# Auto_Temp_Sensor_Second_Way.net
KiCad netlist of a schematic drawn in EAGLE
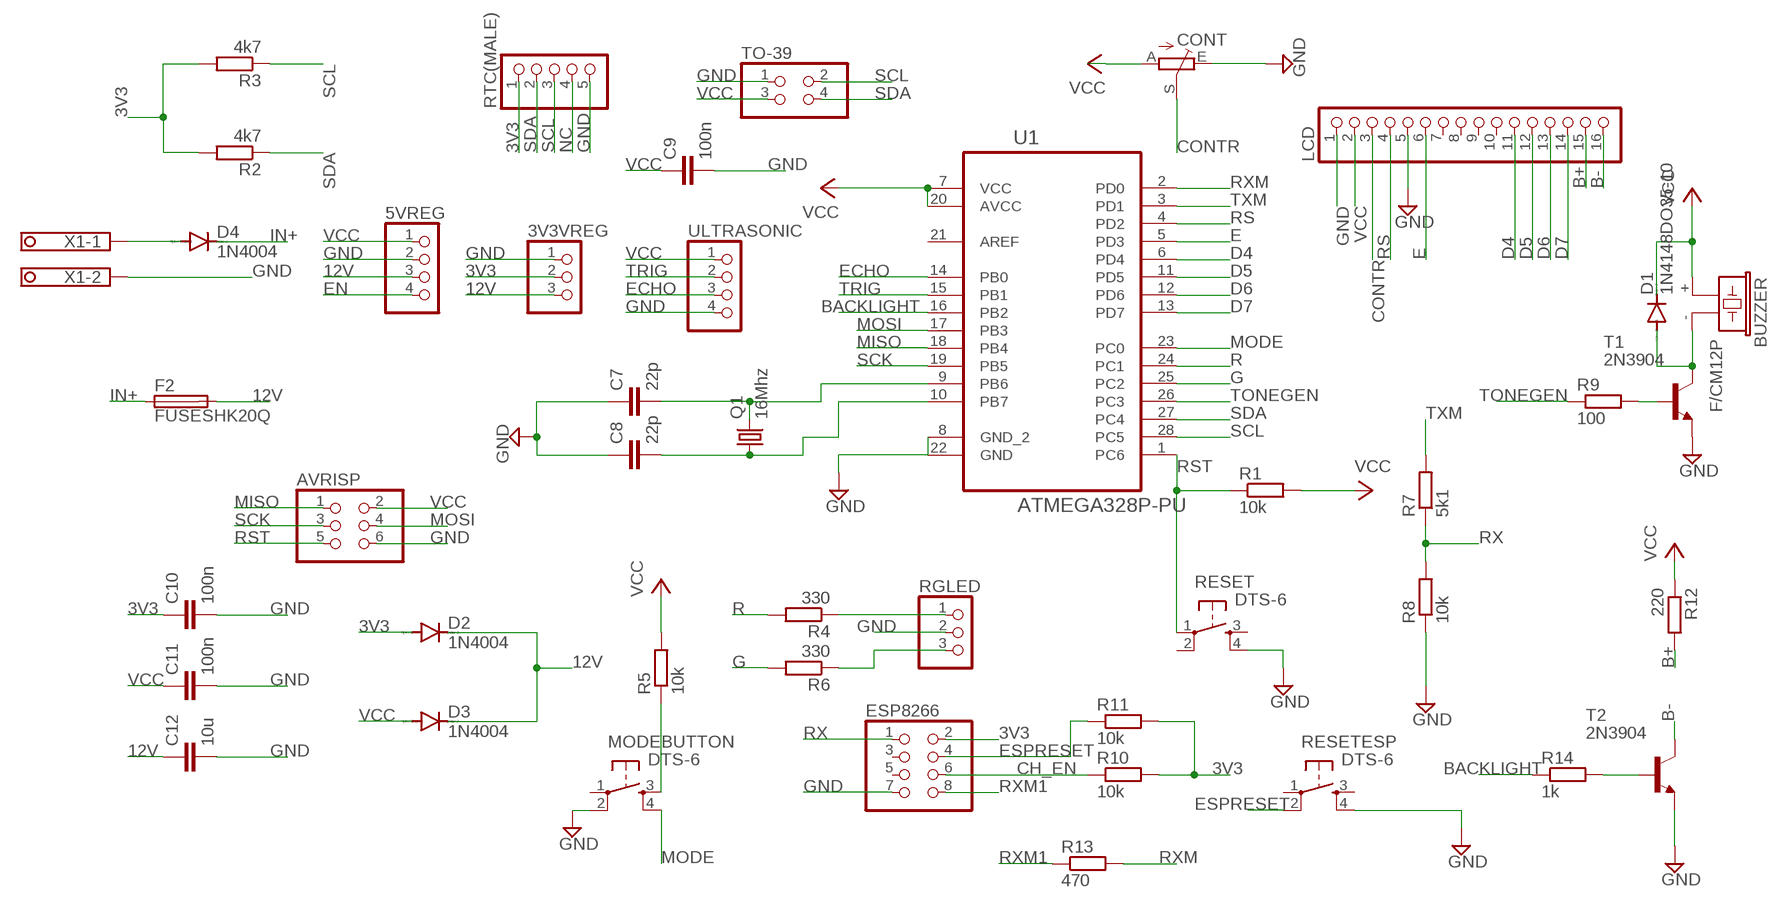
[diagram p0: schematic, sheet 1]

(export (version "E")
  (design (tool "Eeschema 10.0.6"))
  (components
    (comp (ref "3V3VREG")
      (value "PINHD-1X3M")
      (footprint "eagle-import:1X03M")
      (libsource (lib "eagle-import") (part "PINHD-1X3M"))
    )
    (comp (ref "5VREG")
      (value "PINHD-1X4M")
      (footprint "eagle-import:1X04M")
      (libsource (lib "eagle-import") (part "PINHD-1X4M"))
    )
    (comp (ref "AVRISP")
      (value "PINHD-2X3")
      (footprint "eagle-import:2X03")
      (libsource (lib "eagle-import") (part "PINHD-2X3"))
    )
    (comp (ref "BUZZER")
      (value "F/CM12P")
      (footprint "eagle-import:F_CM12P")
      (libsource (lib "eagle-import") (part "F/CM12P"))
    )
    (comp (ref "C7")
      (value "22p")
      (footprint "eagle-import:C050-024X044")
      (libsource (lib "eagle-import") (part "C-EU050-024X044"))
    )
    (comp (ref "C8")
      (value "22p")
      (footprint "eagle-import:C050-024X044")
      (libsource (lib "eagle-import") (part "C-EU050-024X044"))
    )
    (comp (ref "C9")
      (value "100n")
      (footprint "eagle-import:C050-024X044")
      (libsource (lib "eagle-import") (part "C-EU050-024X044"))
    )
    (comp (ref "C10")
      (value "100n")
      (footprint "eagle-import:C050-024X044")
      (libsource (lib "eagle-import") (part "C-EU050-024X044"))
    )
    (comp (ref "C11")
      (value "100n")
      (footprint "eagle-import:C050-024X044")
      (libsource (lib "eagle-import") (part "C-EU050-024X044"))
    )
    (comp (ref "C12")
      (value "10u")
      (footprint "eagle-import:C050-024X044")
      (libsource (lib "eagle-import") (part "C-EU050-024X044"))
    )
    (comp (ref "CONT")
      (value "10k")
      (footprint "eagle-import:B25P")
      (libsource (lib "eagle-import") (part "TRIM_EU-B25P"))
    )
    (comp (ref "D1")
      (value "1N4148DO35-10")
      (footprint "eagle-import:DO35-10")
      (libsource (lib "eagle-import") (part "1N4148DO35-10"))
    )
    (comp (ref "D2")
      (value "1N4004")
      (footprint "eagle-import:DO41-10")
      (libsource (lib "eagle-import") (part "1N4004"))
    )
    (comp (ref "D3")
      (value "1N4004")
      (footprint "eagle-import:DO41-10")
      (libsource (lib "eagle-import") (part "1N4004"))
    )
    (comp (ref "D4")
      (value "1N4004")
      (footprint "eagle-import:DO41-10")
      (libsource (lib "eagle-import") (part "1N4004"))
    )
    (comp (ref "ESP8266")
      (value "PINHD-2X4")
      (footprint "eagle-import:2X04")
      (libsource (lib "eagle-import") (part "PINHD-2X4"))
    )
    (comp (ref "F2")
      (value "FUSESHK20Q")
      (footprint "eagle-import:SHK20Q")
      (libsource (lib "eagle-import") (part "FUSESHK20Q"))
    )
    (comp (ref "LCD")
      (value "PINHD-1X16")
      (footprint "eagle-import:1X16")
      (libsource (lib "eagle-import") (part "PINHD-1X16"))
    )
    (comp (ref "MODEBUTTON")
      (value "DTS-6")
      (footprint "eagle-import:DTS-6")
      (libsource (lib "eagle-import") (part "DTS-6"))
    )
    (comp (ref "Q1")
      (value "16Mhz")
      (footprint "eagle-import:HC49_S")
      (libsource (lib "eagle-import") (part "CRYSTALHC49S"))
    )
    (comp (ref "R1")
      (value "10k")
      (footprint "eagle-import:0207_10")
      (libsource (lib "eagle-import") (part "R-EU_0207/10"))
    )
    (comp (ref "R2")
      (value "4k7")
      (footprint "eagle-import:0207_10")
      (libsource (lib "eagle-import") (part "R-EU_0207/10"))
    )
    (comp (ref "R3")
      (value "4k7")
      (footprint "eagle-import:0207_10")
      (libsource (lib "eagle-import") (part "R-EU_0207/10"))
    )
    (comp (ref "R4")
      (value "330")
      (footprint "eagle-import:0207_10")
      (libsource (lib "eagle-import") (part "R-EU_0207/10"))
    )
    (comp (ref "R5")
      (value "10k")
      (footprint "eagle-import:0207_10")
      (libsource (lib "eagle-import") (part "R-EU_0207/10"))
    )
    (comp (ref "R6")
      (value "330")
      (footprint "eagle-import:0207_10")
      (libsource (lib "eagle-import") (part "R-EU_0207/10"))
    )
    (comp (ref "R7")
      (value "5k1")
      (footprint "eagle-import:0207_10")
      (libsource (lib "eagle-import") (part "R-EU_0207/10"))
    )
    (comp (ref "R8")
      (value "10k")
      (footprint "eagle-import:0207_10")
      (libsource (lib "eagle-import") (part "R-EU_0207/10"))
    )
    (comp (ref "R9")
      (value "100")
      (footprint "eagle-import:0207_10")
      (libsource (lib "eagle-import") (part "R-EU_0207/10"))
    )
    (comp (ref "R10")
      (value "10k")
      (footprint "eagle-import:0207_10")
      (libsource (lib "eagle-import") (part "R-EU_0207/10"))
    )
    (comp (ref "R11")
      (value "10k")
      (footprint "eagle-import:0207_10")
      (libsource (lib "eagle-import") (part "R-EU_0207/10"))
    )
    (comp (ref "R12")
      (value "220")
      (footprint "eagle-import:0207_10")
      (libsource (lib "eagle-import") (part "R-EU_0207/10"))
    )
    (comp (ref "R13")
      (value "470")
      (footprint "eagle-import:0207_10")
      (libsource (lib "eagle-import") (part "R-EU_0207/10"))
    )
    (comp (ref "R14")
      (value "1k")
      (footprint "eagle-import:0207_10")
      (libsource (lib "eagle-import") (part "R-EU_0207/10"))
    )
    (comp (ref "RESET")
      (value "DTS-6")
      (footprint "eagle-import:DTS-6")
      (libsource (lib "eagle-import") (part "DTS-6"))
    )
    (comp (ref "RESETESP")
      (value "DTS-6")
      (footprint "eagle-import:DTS-6")
      (libsource (lib "eagle-import") (part "DTS-6"))
    )
    (comp (ref "RGLED")
      (value "PINHD-1X3M")
      (footprint "eagle-import:1X03M")
      (libsource (lib "eagle-import") (part "PINHD-1X3M"))
    )
    (comp (ref "RTC(MALE)")
      (value "PINHD-1X5")
      (footprint "eagle-import:1X05")
      (libsource (lib "eagle-import") (part "PINHD-1X5"))
    )
    (comp (ref "T1")
      (value "2N3904")
      (footprint "eagle-import:TO92")
      (libsource (lib "eagle-import") (part "2N3904"))
    )
    (comp (ref "T2")
      (value "2N3904")
      (footprint "eagle-import:TO92")
      (libsource (lib "eagle-import") (part "2N3904"))
    )
    (comp (ref "TO-39")
      (value "PINHD-2X2")
      (footprint "eagle-import:2X02")
      (libsource (lib "eagle-import") (part "PINHD-2X2"))
    )
    (comp (ref "U1")
      (value "ATMEGA328P-PU")
      (footprint "eagle-import:DIP254P762X457-28")
      (fields (field (name "MF") "Microchip"))
      (libsource (lib "eagle-import") (part "ATMEGA328P-PU"))
    )
    (comp (ref "ULTRASONIC")
      (value "PINHD-1X4")
      (footprint "eagle-import:1X04")
      (libsource (lib "eagle-import") (part "PINHD-1X4"))
    )
    (comp (ref "X1")
      (value "TERMINAL-BLOCK-3.5MM-2-PIN-LONG-PAD")
      (footprint "eagle-import:TERMINAL-BLOCK-2-PIN-3.5MM-LONG-PAD")
      (libsource (lib "eagle-import") (part "TERMINAL-BLOCK-3.5MM-2-PIN-LONG-PAD"))
    )
  )
  (nets
    (net (code "1") (name "/3V3") (class "Default")
      (node (ref "3V3VREG") (pin "2") (pinfunction "2_2") (pintype "passive"))
      (node (ref "C10") (pin "1") (pinfunction "1_1") (pintype "passive"))
      (node (ref "D2") (pin "A") (pinfunction "A_A") (pintype "passive"))
      (node (ref "ESP8266") (pin "2") (pinfunction "2_2") (pintype "passive"))
      (node (ref "R10") (pin "2") (pinfunction "2_2") (pintype "passive"))
      (node (ref "R11") (pin "2") (pinfunction "2_2") (pintype "passive"))
      (node (ref "R2") (pin "2") (pinfunction "2_2") (pintype "passive"))
      (node (ref "R3") (pin "2") (pinfunction "2_2") (pintype "passive"))
      (node (ref "RTC(MALE)") (pin "1") (pinfunction "1_1") (pintype "passive"))
    )
    (net (code "2") (name "/12V") (class "Default")
      (node (ref "3V3VREG") (pin "3") (pinfunction "3_3") (pintype "passive"))
      (node (ref "5VREG") (pin "3") (pinfunction "3_3") (pintype "passive"))
      (node (ref "C12") (pin "1") (pinfunction "1_1") (pintype "passive"))
      (node (ref "D2") (pin "C") (pinfunction "C_C") (pintype "passive"))
      (node (ref "D3") (pin "C") (pinfunction "C_C") (pintype "passive"))
      (node (ref "F2") (pin "2A") (pinfunction "2_2A") (pintype "passive"))
    )
    (net (code "3") (name "/B+") (class "Default")
      (node (ref "LCD") (pin "15") (pinfunction "15_15") (pintype "passive"))
      (node (ref "R12") (pin "2") (pinfunction "2_2") (pintype "passive"))
    )
    (net (code "4") (name "/B-") (class "Default")
      (node (ref "LCD") (pin "16") (pinfunction "16_16") (pintype "passive"))
      (node (ref "T2") (pin "1") (pinfunction "C_1") (pintype "passive"))
    )
    (net (code "5") (name "/BACKLIGHT") (class "Default")
      (node (ref "R14") (pin "1") (pinfunction "1_1") (pintype "passive"))
      (node (ref "U1") (pin "16") (pinfunction "PB2_16") (pintype "bidirectional"))
    )
    (net (code "6") (name "/CH_EN") (class "Default")
      (node (ref "ESP8266") (pin "6") (pinfunction "6_6") (pintype "passive"))
      (node (ref "R10") (pin "1") (pinfunction "1_1") (pintype "passive"))
    )
    (net (code "7") (name "/CONTR") (class "Default")
      (node (ref "CONT") (pin "S") (pinfunction "S_S") (pintype "passive"))
      (node (ref "LCD") (pin "3") (pinfunction "3_3") (pintype "passive"))
    )
    (net (code "8") (name "/D4") (class "Default")
      (node (ref "LCD") (pin "11") (pinfunction "11_11") (pintype "passive"))
      (node (ref "U1") (pin "6") (pinfunction "PD4_6") (pintype "bidirectional"))
    )
    (net (code "9") (name "/D5") (class "Default")
      (node (ref "LCD") (pin "12") (pinfunction "12_12") (pintype "passive"))
      (node (ref "U1") (pin "11") (pinfunction "PD5_11") (pintype "bidirectional"))
    )
    (net (code "10") (name "/D6") (class "Default")
      (node (ref "LCD") (pin "13") (pinfunction "13_13") (pintype "passive"))
      (node (ref "U1") (pin "12") (pinfunction "PD6_12") (pintype "bidirectional"))
    )
    (net (code "11") (name "/D7") (class "Default")
      (node (ref "LCD") (pin "14") (pinfunction "14_14") (pintype "passive"))
      (node (ref "U1") (pin "13") (pinfunction "PD7_13") (pintype "bidirectional"))
    )
    (net (code "12") (name "/E") (class "Default")
      (node (ref "LCD") (pin "6") (pinfunction "6_6") (pintype "passive"))
      (node (ref "U1") (pin "5") (pinfunction "PD3_5") (pintype "bidirectional"))
    )
    (net (code "13") (name "/ECHO") (class "Default")
      (node (ref "U1") (pin "14") (pinfunction "PB0_14") (pintype "bidirectional"))
      (node (ref "ULTRASONIC") (pin "3") (pinfunction "3_3") (pintype "passive"))
    )
    (net (code "14") (name "/EN") (class "Default")
      (node (ref "5VREG") (pin "4") (pinfunction "4_4") (pintype "passive"))
    )
    (net (code "15") (name "/ESPRESET") (class "Default")
      (node (ref "ESP8266") (pin "4") (pinfunction "4_4") (pintype "passive"))
      (node (ref "R11") (pin "1") (pinfunction "1_1") (pintype "passive"))
      (node (ref "RESETESP") (pin "2") (pinfunction "2_2") (pintype "passive"))
    )
    (net (code "16") (name "/G") (class "Default")
      (node (ref "R6") (pin "2") (pinfunction "2_2") (pintype "passive"))
      (node (ref "U1") (pin "25") (pinfunction "PC2_25") (pintype "bidirectional"))
    )
    (net (code "17") (name "/IN+") (class "Default")
      (node (ref "D4") (pin "C") (pinfunction "C_C") (pintype "passive"))
      (node (ref "F2") (pin "1A") (pinfunction "1_1A") (pintype "passive"))
    )
    (net (code "18") (name "/MISO") (class "Default")
      (node (ref "AVRISP") (pin "1") (pinfunction "1_1") (pintype "passive"))
      (node (ref "U1") (pin "18") (pinfunction "PB4_18") (pintype "bidirectional"))
    )
    (net (code "19") (name "/MODE") (class "Default")
      (node (ref "MODEBUTTON") (pin "4") (pinfunction "4_4") (pintype "passive"))
      (node (ref "U1") (pin "23") (pinfunction "PC0_23") (pintype "bidirectional"))
    )
    (net (code "20") (name "/MOSI") (class "Default")
      (node (ref "AVRISP") (pin "4") (pinfunction "4_4") (pintype "passive"))
      (node (ref "U1") (pin "17") (pinfunction "PB3_17") (pintype "bidirectional"))
    )
    (net (code "21") (name "/NC") (class "Default")
      (node (ref "RTC(MALE)") (pin "4") (pinfunction "4_4") (pintype "passive"))
    )
    (net (code "22") (name "/R") (class "Default")
      (node (ref "R4") (pin "2") (pinfunction "2_2") (pintype "passive"))
      (node (ref "U1") (pin "24") (pinfunction "PC1_24") (pintype "bidirectional"))
    )
    (net (code "23") (name "/RS") (class "Default")
      (node (ref "LCD") (pin "4") (pinfunction "4_4") (pintype "passive"))
      (node (ref "U1") (pin "4") (pinfunction "PD2_4") (pintype "bidirectional"))
    )
    (net (code "24") (name "/RST") (class "Default")
      (node (ref "AVRISP") (pin "5") (pinfunction "5_5") (pintype "passive"))
      (node (ref "R1") (pin "1") (pinfunction "1_1") (pintype "passive"))
      (node (ref "RESET") (pin "1") (pinfunction "1_1") (pintype "passive"))
      (node (ref "U1") (pin "1") (pinfunction "PC6_1") (pintype "bidirectional"))
    )
    (net (code "25") (name "/RX") (class "Default")
      (node (ref "ESP8266") (pin "1") (pinfunction "1_1") (pintype "passive"))
      (node (ref "R7") (pin "1") (pinfunction "1_1") (pintype "passive"))
      (node (ref "R8") (pin "2") (pinfunction "2_2") (pintype "passive"))
    )
    (net (code "26") (name "/RXM") (class "Default")
      (node (ref "R13") (pin "2") (pinfunction "2_2") (pintype "passive"))
      (node (ref "U1") (pin "2") (pinfunction "PD0_2") (pintype "bidirectional"))
    )
    (net (code "27") (name "/RXM1") (class "Default")
      (node (ref "ESP8266") (pin "8") (pinfunction "8_8") (pintype "passive"))
      (node (ref "R13") (pin "1") (pinfunction "1_1") (pintype "passive"))
    )
    (net (code "28") (name "/SCK") (class "Default")
      (node (ref "AVRISP") (pin "3") (pinfunction "3_3") (pintype "passive"))
      (node (ref "U1") (pin "19") (pinfunction "PB5_19") (pintype "bidirectional"))
    )
    (net (code "29") (name "/SCL") (class "Default")
      (node (ref "R3") (pin "1") (pinfunction "1_1") (pintype "passive"))
      (node (ref "RTC(MALE)") (pin "3") (pinfunction "3_3") (pintype "passive"))
      (node (ref "TO-39") (pin "2") (pinfunction "2_2") (pintype "passive"))
      (node (ref "U1") (pin "28") (pinfunction "PC5_28") (pintype "bidirectional"))
    )
    (net (code "30") (name "/SDA") (class "Default")
      (node (ref "R2") (pin "1") (pinfunction "1_1") (pintype "passive"))
      (node (ref "RTC(MALE)") (pin "2") (pinfunction "2_2") (pintype "passive"))
      (node (ref "TO-39") (pin "4") (pinfunction "4_4") (pintype "passive"))
      (node (ref "U1") (pin "27") (pinfunction "PC4_27") (pintype "bidirectional"))
    )
    (net (code "31") (name "/TONEGEN") (class "Default")
      (node (ref "R9") (pin "1") (pinfunction "1_1") (pintype "passive"))
      (node (ref "U1") (pin "26") (pinfunction "PC3_26") (pintype "bidirectional"))
    )
    (net (code "32") (name "/TRIG") (class "Default")
      (node (ref "U1") (pin "15") (pinfunction "PB1_15") (pintype "bidirectional"))
      (node (ref "ULTRASONIC") (pin "2") (pinfunction "2_2") (pintype "passive"))
    )
    (net (code "33") (name "/TXM") (class "Default")
      (node (ref "R7") (pin "2") (pinfunction "2_2") (pintype "passive"))
      (node (ref "U1") (pin "3") (pinfunction "PD1_3") (pintype "bidirectional"))
    )
    (net (code "34") (name "GND") (class "Default")
      (node (ref "3V3VREG") (pin "1") (pinfunction "1_1") (pintype "passive"))
      (node (ref "5VREG") (pin "2") (pinfunction "2_2") (pintype "passive"))
      (node (ref "AVRISP") (pin "6") (pinfunction "6_6") (pintype "passive"))
      (node (ref "C10") (pin "2") (pinfunction "2_2") (pintype "passive"))
      (node (ref "C11") (pin "2") (pinfunction "2_2") (pintype "passive"))
      (node (ref "C12") (pin "2") (pinfunction "2_2") (pintype "passive"))
      (node (ref "C7") (pin "1") (pinfunction "1_1") (pintype "passive"))
      (node (ref "C8") (pin "1") (pinfunction "1_1") (pintype "passive"))
      (node (ref "C9") (pin "2") (pinfunction "2_2") (pintype "passive"))
      (node (ref "CONT") (pin "E") (pinfunction "E_E") (pintype "passive"))
      (node (ref "ESP8266") (pin "7") (pinfunction "7_7") (pintype "passive"))
      (node (ref "LCD") (pin "1") (pinfunction "1_1") (pintype "passive"))
      (node (ref "LCD") (pin "5") (pinfunction "5_5") (pintype "passive"))
      (node (ref "MODEBUTTON") (pin "2") (pinfunction "2_2") (pintype "passive"))
      (node (ref "R8") (pin "1") (pinfunction "1_1") (pintype "passive"))
      (node (ref "RESET") (pin "4") (pinfunction "4_4") (pintype "passive"))
      (node (ref "RESETESP") (pin "4") (pinfunction "4_4") (pintype "passive"))
      (node (ref "RGLED") (pin "2") (pinfunction "2_2") (pintype "passive"))
      (node (ref "RTC(MALE)") (pin "5") (pinfunction "5_5") (pintype "passive"))
      (node (ref "T1") (pin "3") (pinfunction "E_3") (pintype "passive"))
      (node (ref "T2") (pin "3") (pinfunction "E_3") (pintype "passive"))
      (node (ref "TO-39") (pin "1") (pinfunction "1_1") (pintype "passive"))
      (node (ref "U1") (pin "22") (pinfunction "GND_22") (pintype "passive"))
      (node (ref "U1") (pin "8") (pinfunction "GND_2_8") (pintype "passive"))
      (node (ref "ULTRASONIC") (pin "4") (pinfunction "4_4") (pintype "passive"))
      (node (ref "X1") (pin "2") (pinfunction "K_2") (pintype "passive"))
    )
    (net (code "35") (name "Net-(BUZZER-2)") (class "Default")
      (node (ref "BUZZER") (pin "-") (pinfunction "2_-") (pintype "passive"))
      (node (ref "D1") (pin "A") (pinfunction "A_A") (pintype "passive"))
      (node (ref "T1") (pin "1") (pinfunction "C_1") (pintype "passive"))
    )
    (net (code "36") (name "Net-(MODEBUTTON-Pad3)") (class "Default")
      (node (ref "MODEBUTTON") (pin "3") (pinfunction "3_3") (pintype "passive"))
      (node (ref "R5") (pin "1") (pinfunction "1_1") (pintype "passive"))
    )
    (net (code "37") (name "Net-(R4-Pad1)") (class "Default")
      (node (ref "R4") (pin "1") (pinfunction "1_1") (pintype "passive"))
      (node (ref "RGLED") (pin "1") (pinfunction "1_1") (pintype "passive"))
    )
    (net (code "38") (name "Net-(R6-Pad1)") (class "Default")
      (node (ref "R6") (pin "1") (pinfunction "1_1") (pintype "passive"))
      (node (ref "RGLED") (pin "3") (pinfunction "3_3") (pintype "passive"))
    )
    (net (code "39") (name "Net-(T1-B)") (class "Default")
      (node (ref "R9") (pin "2") (pinfunction "2_2") (pintype "passive"))
      (node (ref "T1") (pin "2") (pinfunction "B_2") (pintype "passive"))
    )
    (net (code "40") (name "Net-(T2-B)") (class "Default")
      (node (ref "R14") (pin "2") (pinfunction "2_2") (pintype "passive"))
      (node (ref "T2") (pin "2") (pinfunction "B_2") (pintype "passive"))
    )
    (net (code "41") (name "Net-(U1-PB6)") (class "Default")
      (node (ref "C7") (pin "2") (pinfunction "2_2") (pintype "passive"))
      (node (ref "Q1") (pin "2") (pinfunction "2_2") (pintype "passive"))
      (node (ref "U1") (pin "9") (pinfunction "PB6_9") (pintype "bidirectional"))
    )
    (net (code "42") (name "Net-(U1-PB7)") (class "Default")
      (node (ref "C8") (pin "2") (pinfunction "2_2") (pintype "passive"))
      (node (ref "Q1") (pin "1") (pinfunction "1_1") (pintype "passive"))
      (node (ref "U1") (pin "10") (pinfunction "PB7_10") (pintype "bidirectional"))
    )
    (net (code "43") (name "Net-(X1A-K)") (class "Default")
      (node (ref "D4") (pin "A") (pinfunction "A_A") (pintype "passive"))
      (node (ref "X1") (pin "1") (pinfunction "K_1") (pintype "passive"))
    )
    (net (code "44") (name "VCC") (class "Default")
      (node (ref "5VREG") (pin "1") (pinfunction "1_1") (pintype "passive"))
      (node (ref "AVRISP") (pin "2") (pinfunction "2_2") (pintype "passive"))
      (node (ref "BUZZER") (pin "+") (pinfunction "1_+") (pintype "passive"))
      (node (ref "C11") (pin "1") (pinfunction "1_1") (pintype "passive"))
      (node (ref "C9") (pin "1") (pinfunction "1_1") (pintype "passive"))
      (node (ref "CONT") (pin "A") (pinfunction "A_A") (pintype "passive"))
      (node (ref "D1") (pin "C") (pinfunction "C_C") (pintype "passive"))
      (node (ref "D3") (pin "A") (pinfunction "A_A") (pintype "passive"))
      (node (ref "LCD") (pin "2") (pinfunction "2_2") (pintype "passive"))
      (node (ref "R1") (pin "2") (pinfunction "2_2") (pintype "passive"))
      (node (ref "R12") (pin "1") (pinfunction "1_1") (pintype "passive"))
      (node (ref "R5") (pin "2") (pinfunction "2_2") (pintype "passive"))
      (node (ref "TO-39") (pin "3") (pinfunction "3_3") (pintype "passive"))
      (node (ref "U1") (pin "20") (pinfunction "AVCC_20") (pintype "power_in"))
      (node (ref "U1") (pin "7") (pinfunction "VCC_7") (pintype "power_in"))
      (node (ref "ULTRASONIC") (pin "1") (pinfunction "1_1") (pintype "passive"))
    )
    (net (code "45") (name "unconnected-(ESP8266-Pad3)") (class "Default")
      (node (ref "ESP8266") (pin "3") (pinfunction "3_3") (pintype "passive"))
    )
    (net (code "46") (name "unconnected-(ESP8266-Pad5)") (class "Default")
      (node (ref "ESP8266") (pin "5") (pinfunction "5_5") (pintype "passive"))
    )
    (net (code "47") (name "unconnected-(LCD-Pad7)") (class "Default")
      (node (ref "LCD") (pin "7") (pinfunction "7_7") (pintype "passive"))
    )
    (net (code "48") (name "unconnected-(LCD-Pad8)") (class "Default")
      (node (ref "LCD") (pin "8") (pinfunction "8_8") (pintype "passive"))
    )
    (net (code "49") (name "unconnected-(LCD-Pad9)") (class "Default")
      (node (ref "LCD") (pin "9") (pinfunction "9_9") (pintype "passive"))
    )
    (net (code "50") (name "unconnected-(LCD-Pad10)") (class "Default")
      (node (ref "LCD") (pin "10") (pinfunction "10_10") (pintype "passive"))
    )
    (net (code "51") (name "unconnected-(MODEBUTTON-Pad1)") (class "Default")
      (node (ref "MODEBUTTON") (pin "1") (pinfunction "1_1") (pintype "passive"))
    )
    (net (code "52") (name "unconnected-(RESET-Pad2)") (class "Default")
      (node (ref "RESET") (pin "2") (pinfunction "2_2") (pintype "passive"))
    )
    (net (code "53") (name "unconnected-(RESET-Pad3)") (class "Default")
      (node (ref "RESET") (pin "3") (pinfunction "3_3") (pintype "passive"))
    )
    (net (code "54") (name "unconnected-(RESETESP-Pad1)") (class "Default")
      (node (ref "RESETESP") (pin "1") (pinfunction "1_1") (pintype "passive"))
    )
    (net (code "55") (name "unconnected-(RESETESP-Pad3)") (class "Default")
      (node (ref "RESETESP") (pin "3") (pinfunction "3_3") (pintype "passive"))
    )
    (net (code "56") (name "unconnected-(U1-AREF-Pad21)") (class "Default")
      (node (ref "U1") (pin "21") (pinfunction "AREF_21") (pintype "input"))
    )
  )
)
